# shdn_circuit.net
KiCad netlist of a schematic drawn in Altium Designer
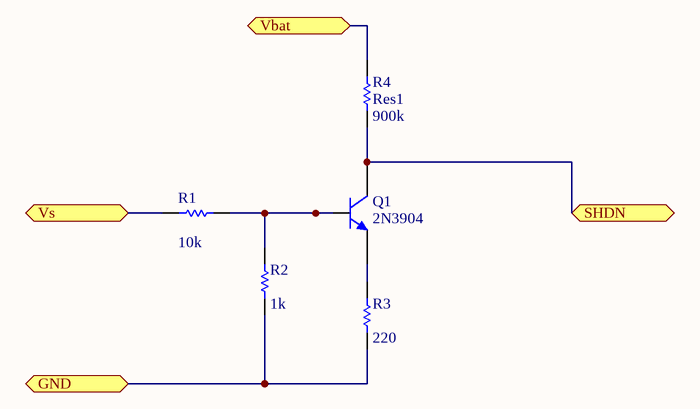
[diagram p0: shdn_circuit.SchDoc]

(export (version "E")
  (design (tool "Eeschema 10.0.6"))
  (components
    (comp (ref "Q1")
      (value "2N3904")
      (footprint "TO-92A")
      (description "NPN General Purpose Amplifier")
      (fields (field (name "PUBLISHER") "Altium Limited"))
      (libsource (lib "Miscellaneous Devices") (part "2N3904"))
    )
    (comp (ref "R1")
      (value "10k")
      (footprint "AXIAL-0.3")
      (description "Resistor")
      (fields (field (name "Comment") "Res1") (field (name "PUBLISHER") "Altium Limited"))
      (libsource (lib "Miscellaneous Devices") (part "Res1"))
    )
    (comp (ref "R2")
      (value "1k")
      (footprint "AXIAL-0.3")
      (description "Resistor")
      (fields (field (name "Comment") "Res1") (field (name "PUBLISHER") "Altium Limited"))
      (libsource (lib "Miscellaneous Devices") (part "Res1"))
    )
    (comp (ref "R3")
      (value "220")
      (footprint "AXIAL-0.3")
      (description "Resistor")
      (fields (field (name "Comment") "Res1") (field (name "PUBLISHER") "Altium Limited"))
      (libsource (lib "Miscellaneous Devices") (part "Res1"))
    )
    (comp (ref "R4")
      (value "Res1")
      (footprint "AXIAL-0.3")
      (description "Resistor")
      (fields (field (name "ALTIUM_VALUE") "900k") (field (name "PUBLISHER") "Altium Limited"))
      (libsource (lib "Miscellaneous Devices") (part "Res1"))
    )
  )
  (nets
    (net (code "1") (name "/GND") (class "Default")
      (node (ref "R2") (pin "1") (pinfunction "1_1") (pintype "passive"))
      (node (ref "R3") (pin "1") (pinfunction "1_1") (pintype "passive"))
    )
    (net (code "2") (name "/SHDN") (class "Default")
      (node (ref "Q1") (pin "3") (pinfunction "C_3") (pintype "passive"))
      (node (ref "R4") (pin "2") (pinfunction "2_2") (pintype "passive"))
    )
    (net (code "3") (name "/Vbat") (class "Default")
      (node (ref "R4") (pin "1") (pinfunction "1_1") (pintype "passive"))
    )
    (net (code "4") (name "/Vs") (class "Default")
      (node (ref "R1") (pin "1") (pinfunction "1_1") (pintype "passive"))
    )
    (net (code "5") (name "Net-(Q1-B)") (class "Default")
      (node (ref "Q1") (pin "2") (pinfunction "B_2") (pintype "passive"))
      (node (ref "R1") (pin "2") (pinfunction "2_2") (pintype "passive"))
      (node (ref "R2") (pin "2") (pinfunction "2_2") (pintype "passive"))
    )
    (net (code "6") (name "Net-(Q1-E)") (class "Default")
      (node (ref "Q1") (pin "1") (pinfunction "E_1") (pintype "passive"))
      (node (ref "R3") (pin "2") (pinfunction "2_2") (pintype "passive"))
    )
  )
)
